# shield.net
KiCad netlist of a schematic drawn in Altium Designer
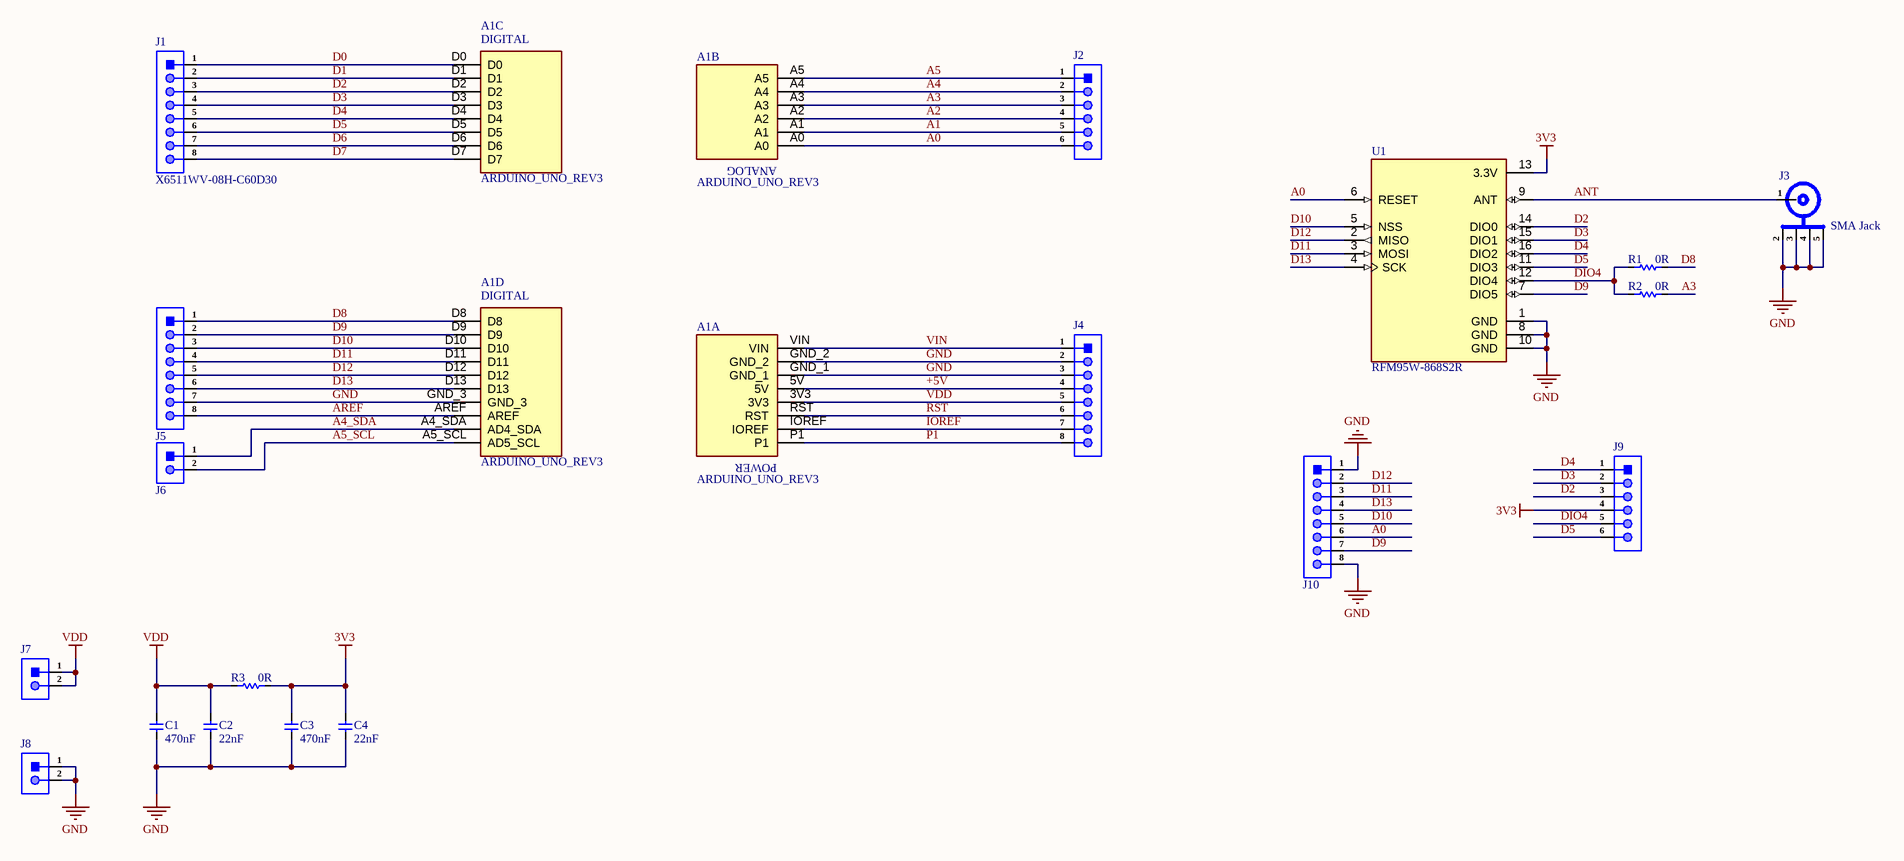
[diagram p0: shield.SchDoc]

(export (version "E")
  (design (tool "Eeschema 10.0.6"))
  (components
    (comp (ref "A1")
      (value "ARDUINO_UNO_REV3")
      (footprint "ARDUINO_ARDUINO_UNO_REV3")
      (description "Microcontroller board based on the ATmega328P.")
      (fields (field (name "MF") "Arduino") (field (name "MP") "ARDUINO UNO REV3"))
      (libsource (lib "") (part "ARDUINO_UNO_REV3_1"))
    )
    (comp (ref "C1")
      (value "470nF")
      (footprint "Cap-0402")
      (description "CAP CER 0.47UF 16V X5R 0402")
      (fields
        (field (name "MANUFACTURER") "Yageo")
        (field (name "MANUFACTURER PART NUMBER") "CC0402KRX5R7BB474")
      )
      (libsource (lib "eSpark Libraries") (part "CC0402KRX5R7BB474"))
    )
    (comp (ref "C2")
      (value "22nF")
      (footprint "Cap-0402")
      (description "CAP CER 0.022UF 16V X7R 0402")
      (fields
        (field (name "MANUFACTURER") "Yageo")
        (field (name "MANUFACTURER PART NUMBER") "CC0402JRX7R7BB223")
      )
      (libsource (lib "eSpark Libraries") (part "CC0402JRX7R7BB223"))
    )
    (comp (ref "C3")
      (value "470nF")
      (footprint "Cap-0402")
      (description "CAP CER 0.47UF 16V X5R 0402")
      (fields
        (field (name "MANUFACTURER") "Yageo")
        (field (name "MANUFACTURER PART NUMBER") "CC0402KRX5R7BB474")
      )
      (libsource (lib "eSpark Libraries") (part "CC0402KRX5R7BB474"))
    )
    (comp (ref "C4")
      (value "22nF")
      (footprint "Cap-0402")
      (description "CAP CER 0.022UF 16V X7R 0402")
      (fields
        (field (name "MANUFACTURER") "Yageo")
        (field (name "MANUFACTURER PART NUMBER") "CC0402JRX7R7BB223")
      )
      (libsource (lib "eSpark Libraries") (part "CC0402JRX7R7BB223"))
    )
    (comp (ref "J1")
      (value "X6511WV-08H-C60D30")
      (footprint "HDR 1x8 TH male")
      (fields (field (name "MANUFACTURER") "XKB") (field (name "LCSC PART NUMBER") "C706880"))
      (libsource (lib "") (part "X6511WV-08H-C60D30_1"))
    )
    (comp (ref "J2")
      (value "X6511WV-06H-C60D30")
      (footprint "HDR1X6_")
      (fields (field (name "MANUFACTURER") "XKB") (field (name "LCSC PART NUMBER") "C706878"))
      (libsource (lib "eSpark Libraries") (part "X6511WV-06H-C60D30"))
    )
    (comp (ref "J3")
      (value "SMA Jack")
      (footprint "CON-SMA-EDGE_S")
      (description "Sma Female Connector, Pcb Edge Mount Rohs Compliant: Yes")
      (fields
        (field (name "MANUFACTURER") "RF Solutions")
        (field (name "MANUFACTURER PART NUMBER") "CON-SMA-EDGE-S")
      )
      (libsource (lib "eSpark Libraries") (part "CON-SMA-EDGE-S"))
    )
    (comp (ref "J4")
      (value "X6511WV-08H-C60D30")
      (footprint "HDR 1x8 TH male")
      (fields (field (name "MANUFACTURER") "XKB") (field (name "LCSC PART NUMBER") "C706880"))
      (libsource (lib "eSpark Libraries") (part "X6511WV-08H-C60D30"))
    )
    (comp (ref "J5")
      (value "X6511WV-08H-C60D30")
      (footprint "HDR 1x8 TH male")
      (fields (field (name "MANUFACTURER") "XKB") (field (name "LCSC PART NUMBER") "C706880"))
      (libsource (lib "") (part "X6511WV-08H-C60D30_1"))
    )
    (comp (ref "J6")
      (value "X6511WV-02H-C60D30")
      (footprint "HDR1X2_")
      (fields (field (name "MANUFACTURER") "XKB") (field (name "LCSC PART NUMBER") "C706874"))
      (libsource (lib "eSpark Libraries") (part "X6511WV-02H-C60D30"))
    )
    (comp (ref "J7")
      (value "X6511WV-02H-C60D30")
      (footprint "HDR1X2_")
      (fields (field (name "MANUFACTURER") "XKB") (field (name "LCSC PART NUMBER") "C706874"))
      (libsource (lib "eSpark Libraries") (part "X6511WV-02H-C60D30"))
    )
    (comp (ref "J8")
      (value "X6511WV-02H-C60D30")
      (footprint "HDR1X2_")
      (fields (field (name "MANUFACTURER") "XKB") (field (name "LCSC PART NUMBER") "C706874"))
      (libsource (lib "eSpark Libraries") (part "X6511WV-02H-C60D30"))
    )
    (comp (ref "J9")
      (value "X6511WV-06H-C60D30")
      (footprint "HDR1X6_")
      (fields (field (name "MANUFACTURER") "XKB") (field (name "LCSC PART NUMBER") "C706878"))
      (libsource (lib "eSpark Libraries") (part "X6511WV-06H-C60D30"))
    )
    (comp (ref "J10")
      (value "X6511WV-08H-C60D30")
      (footprint "HDR 1x8 TH male")
      (fields (field (name "MANUFACTURER") "XKB") (field (name "LCSC PART NUMBER") "C706880"))
      (libsource (lib "") (part "X6511WV-08H-C60D30_1"))
    )
    (comp (ref "R1")
      (value "0R")
      (footprint "Res-0603")
      (description "RES SMD 0R, 1%, 0.1W, 0603")
      (fields
        (field (name "MANUFACTURER") "Yageo")
        (field (name "MANUFACTURER PART NUMBER") "RC0603FR-070RL")
      )
      (libsource (lib "eSpark Libraries") (part "RC0603FR-070RL"))
    )
    (comp (ref "R2")
      (value "0R")
      (footprint "Res-0603")
      (description "RES SMD 0R, 1%, 0.1W, 0603")
      (fields
        (field (name "MANUFACTURER") "Yageo")
        (field (name "MANUFACTURER PART NUMBER") "RC0603FR-070RL")
      )
      (libsource (lib "eSpark Libraries") (part "RC0603FR-070RL"))
    )
    (comp (ref "R3")
      (value "0R")
      (footprint "Res-0603")
      (description "RES SMD 0R, 1%, 0.1W, 0603")
      (fields
        (field (name "MANUFACTURER") "Yageo")
        (field (name "MANUFACTURER PART NUMBER") "RC0603FR-070RL")
      )
      (libsource (lib "eSpark Libraries") (part "RC0603FR-070RL"))
    )
    (comp (ref "U1")
      (value "RFM95W-868S2R")
      (footprint "MODULE_RFM95W-868S2R")
      (description "Module: transceiver; RF; FSK,GFSK,GMSK,LoRa,MSK,OOK; 868MHz; SMD")
      (fields (field (name "MF") "Hope Microelectronics"))
      (libsource (lib "RFM95W-868S2R") (part "RFM95W-868S2R"))
    )
  )
  (nets
    (net (code "1") (name "/+5V") (class "Default")
      (node (ref "A1") (pin "5V") (pinfunction "5V_5V") (pintype "power_in"))
      (node (ref "J4") (pin "4") (pinfunction "4_4") (pintype "passive"))
    )
    (net (code "2") (name "/A0") (class "Default")
      (node (ref "A1") (pin "A0") (pinfunction "A0_A0") (pintype "passive"))
      (node (ref "J10") (pin "6") (pinfunction "6_6") (pintype "passive"))
      (node (ref "J2") (pin "6") (pinfunction "6_6") (pintype "passive"))
      (node (ref "U1") (pin "6") (pinfunction "RESET_6") (pintype "input"))
    )
    (net (code "3") (name "/A1") (class "Default")
      (node (ref "A1") (pin "A1") (pinfunction "A1_A1") (pintype "passive"))
      (node (ref "J2") (pin "5") (pinfunction "5_5") (pintype "passive"))
    )
    (net (code "4") (name "/A2") (class "Default")
      (node (ref "A1") (pin "A2") (pinfunction "A2_A2") (pintype "passive"))
      (node (ref "J2") (pin "4") (pinfunction "4_4") (pintype "passive"))
    )
    (net (code "5") (name "/A3") (class "Default")
      (node (ref "A1") (pin "A3") (pinfunction "A3_A3") (pintype "passive"))
      (node (ref "J2") (pin "3") (pinfunction "3_3") (pintype "passive"))
      (node (ref "R2") (pin "2") (pinfunction "2_2") (pintype "passive"))
    )
    (net (code "6") (name "/A4") (class "Default")
      (node (ref "A1") (pin "A4") (pinfunction "A4_A4") (pintype "passive"))
      (node (ref "J2") (pin "2") (pinfunction "2_2") (pintype "passive"))
    )
    (net (code "7") (name "/A4_SDA") (class "Default")
      (node (ref "A1") (pin "A4_SDA") (pinfunction "AD4_SDA_A4_SDA") (pintype "bidirectional"))
      (node (ref "J6") (pin "1") (pinfunction "1_1") (pintype "passive"))
    )
    (net (code "8") (name "/A5") (class "Default")
      (node (ref "A1") (pin "A5") (pinfunction "A5_A5") (pintype "passive"))
      (node (ref "J2") (pin "1") (pinfunction "1_1") (pintype "passive"))
    )
    (net (code "9") (name "/A5_SCL") (class "Default")
      (node (ref "A1") (pin "A5_SCL") (pinfunction "AD5_SCL_A5_SCL") (pintype "bidirectional"))
      (node (ref "J6") (pin "2") (pinfunction "2_2") (pintype "passive"))
    )
    (net (code "10") (name "/ANT") (class "Default")
      (node (ref "J3") (pin "1") (pinfunction "ANT_1") (pintype "passive"))
      (node (ref "U1") (pin "9") (pinfunction "ANT_9") (pintype "bidirectional"))
    )
    (net (code "11") (name "/AREF") (class "Default")
      (node (ref "A1") (pin "AREF") (pinfunction "AREF_AREF") (pintype "bidirectional"))
      (node (ref "J5") (pin "8") (pinfunction "8_8") (pintype "passive"))
    )
    (net (code "12") (name "/D0") (class "Default")
      (node (ref "A1") (pin "D0") (pinfunction "D0_D0") (pintype "passive"))
      (node (ref "J1") (pin "1") (pinfunction "1_1") (pintype "passive"))
    )
    (net (code "13") (name "/D1") (class "Default")
      (node (ref "A1") (pin "D1") (pinfunction "D1_D1") (pintype "passive"))
      (node (ref "J1") (pin "2") (pinfunction "2_2") (pintype "passive"))
    )
    (net (code "14") (name "/D2") (class "Default")
      (node (ref "A1") (pin "D2") (pinfunction "D2_D2") (pintype "passive"))
      (node (ref "J1") (pin "3") (pinfunction "3_3") (pintype "passive"))
      (node (ref "J9") (pin "3") (pinfunction "3_3") (pintype "passive"))
      (node (ref "U1") (pin "14") (pinfunction "DIO0_14") (pintype "bidirectional"))
    )
    (net (code "15") (name "/D3") (class "Default")
      (node (ref "A1") (pin "D3") (pinfunction "D3_D3") (pintype "passive"))
      (node (ref "J1") (pin "4") (pinfunction "4_4") (pintype "passive"))
      (node (ref "J9") (pin "2") (pinfunction "2_2") (pintype "passive"))
      (node (ref "U1") (pin "15") (pinfunction "DIO1_15") (pintype "bidirectional"))
    )
    (net (code "16") (name "/D4") (class "Default")
      (node (ref "A1") (pin "D4") (pinfunction "D4_D4") (pintype "passive"))
      (node (ref "J1") (pin "5") (pinfunction "5_5") (pintype "passive"))
      (node (ref "J9") (pin "1") (pinfunction "1_1") (pintype "passive"))
      (node (ref "U1") (pin "16") (pinfunction "DIO2_16") (pintype "bidirectional"))
    )
    (net (code "17") (name "/D5") (class "Default")
      (node (ref "A1") (pin "D5") (pinfunction "D5_D5") (pintype "passive"))
      (node (ref "J1") (pin "6") (pinfunction "6_6") (pintype "passive"))
      (node (ref "J9") (pin "6") (pinfunction "6_6") (pintype "passive"))
      (node (ref "U1") (pin "11") (pinfunction "DIO3_11") (pintype "bidirectional"))
    )
    (net (code "18") (name "/D6") (class "Default")
      (node (ref "A1") (pin "D6") (pinfunction "D6_D6") (pintype "passive"))
      (node (ref "J1") (pin "7") (pinfunction "7_7") (pintype "passive"))
    )
    (net (code "19") (name "/D7") (class "Default")
      (node (ref "A1") (pin "D7") (pinfunction "D7_D7") (pintype "passive"))
      (node (ref "J1") (pin "8") (pinfunction "8_8") (pintype "passive"))
    )
    (net (code "20") (name "/D8") (class "Default")
      (node (ref "A1") (pin "D8") (pinfunction "D8_D8") (pintype "bidirectional"))
      (node (ref "J5") (pin "1") (pinfunction "1_1") (pintype "passive"))
      (node (ref "R1") (pin "2") (pinfunction "2_2") (pintype "passive"))
    )
    (net (code "21") (name "/D9") (class "Default")
      (node (ref "A1") (pin "D9") (pinfunction "D9_D9") (pintype "bidirectional"))
      (node (ref "J10") (pin "7") (pinfunction "7_7") (pintype "passive"))
      (node (ref "J5") (pin "2") (pinfunction "2_2") (pintype "passive"))
      (node (ref "U1") (pin "7") (pinfunction "DIO5_7") (pintype "bidirectional"))
    )
    (net (code "22") (name "/D10") (class "Default")
      (node (ref "A1") (pin "D10") (pinfunction "D10_D10") (pintype "bidirectional"))
      (node (ref "J10") (pin "5") (pinfunction "5_5") (pintype "passive"))
      (node (ref "J5") (pin "3") (pinfunction "3_3") (pintype "passive"))
      (node (ref "U1") (pin "5") (pinfunction "NSS_5") (pintype "input"))
    )
    (net (code "23") (name "/D11") (class "Default")
      (node (ref "A1") (pin "D11") (pinfunction "D11_D11") (pintype "bidirectional"))
      (node (ref "J10") (pin "3") (pinfunction "3_3") (pintype "passive"))
      (node (ref "J5") (pin "4") (pinfunction "4_4") (pintype "passive"))
      (node (ref "U1") (pin "3") (pinfunction "MOSI_3") (pintype "input"))
    )
    (net (code "24") (name "/D12") (class "Default")
      (node (ref "A1") (pin "D12") (pinfunction "D12_D12") (pintype "bidirectional"))
      (node (ref "J10") (pin "2") (pinfunction "2_2") (pintype "passive"))
      (node (ref "J5") (pin "5") (pinfunction "5_5") (pintype "passive"))
      (node (ref "U1") (pin "2") (pinfunction "MISO_2") (pintype "output"))
    )
    (net (code "25") (name "/D13") (class "Default")
      (node (ref "A1") (pin "D13") (pinfunction "D13_D13") (pintype "bidirectional"))
      (node (ref "J10") (pin "4") (pinfunction "4_4") (pintype "passive"))
      (node (ref "J5") (pin "6") (pinfunction "6_6") (pintype "passive"))
      (node (ref "U1") (pin "4") (pinfunction "SCK_4") (pintype "input"))
    )
    (net (code "26") (name "/DIO4") (class "Default")
      (node (ref "J9") (pin "5") (pinfunction "5_5") (pintype "passive"))
      (node (ref "R1") (pin "1") (pinfunction "1_1") (pintype "passive"))
      (node (ref "R2") (pin "1") (pinfunction "1_1") (pintype "passive"))
      (node (ref "U1") (pin "12") (pinfunction "DIO4_12") (pintype "bidirectional"))
    )
    (net (code "27") (name "/IOREF") (class "Default")
      (node (ref "A1") (pin "IOREF") (pinfunction "IOREF_IOREF") (pintype "passive"))
      (node (ref "J4") (pin "7") (pinfunction "7_7") (pintype "passive"))
    )
    (net (code "28") (name "/P1") (class "Default")
      (node (ref "A1") (pin "P1") (pinfunction "P1_P1") (pintype "passive"))
      (node (ref "J4") (pin "8") (pinfunction "8_8") (pintype "passive"))
    )
    (net (code "29") (name "/RST") (class "Default")
      (node (ref "A1") (pin "RST") (pinfunction "RST_RST") (pintype "passive"))
      (node (ref "J4") (pin "6") (pinfunction "6_6") (pintype "passive"))
    )
    (net (code "30") (name "/VIN") (class "Default")
      (node (ref "A1") (pin "VIN") (pinfunction "VIN_VIN") (pintype "power_in"))
      (node (ref "J4") (pin "1") (pinfunction "1_1") (pintype "passive"))
    )
    (net (code "31") (name "3V3") (class "Default")
      (node (ref "C3") (pin "2") (pinfunction "2_2") (pintype "passive"))
      (node (ref "C4") (pin "2") (pinfunction "2_2") (pintype "passive"))
      (node (ref "J9") (pin "4") (pinfunction "4_4") (pintype "passive"))
      (node (ref "R3") (pin "2") (pinfunction "2_2") (pintype "passive"))
      (node (ref "U1") (pin "13") (pinfunction "3.3V_13") (pintype "power_in"))
    )
    (net (code "32") (name "GND") (class "Default")
      (node (ref "A1") (pin "GND_1") (pinfunction "GND_1_GND_1") (pintype "power_in"))
      (node (ref "A1") (pin "GND_2") (pinfunction "GND_2_GND_2") (pintype "power_in"))
      (node (ref "A1") (pin "GND_3") (pinfunction "GND_3_GND_3") (pintype "power_in"))
      (node (ref "C1") (pin "1") (pinfunction "1_1") (pintype "passive"))
      (node (ref "C2") (pin "1") (pinfunction "1_1") (pintype "passive"))
      (node (ref "C3") (pin "1") (pinfunction "1_1") (pintype "passive"))
      (node (ref "C4") (pin "1") (pinfunction "1_1") (pintype "passive"))
      (node (ref "J10") (pin "1") (pinfunction "1_1") (pintype "passive"))
      (node (ref "J10") (pin "8") (pinfunction "8_8") (pintype "passive"))
      (node (ref "J3") (pin "2") (pinfunction "GND_2") (pintype "passive"))
      (node (ref "J3") (pin "3") (pinfunction "GND_3") (pintype "passive"))
      (node (ref "J3") (pin "4") (pinfunction "GND_4") (pintype "passive"))
      (node (ref "J3") (pin "5") (pinfunction "GND_5") (pintype "passive"))
      (node (ref "J4") (pin "2") (pinfunction "2_2") (pintype "passive"))
      (node (ref "J4") (pin "3") (pinfunction "3_3") (pintype "passive"))
      (node (ref "J5") (pin "7") (pinfunction "7_7") (pintype "passive"))
      (node (ref "J8") (pin "1") (pinfunction "1_1") (pintype "passive"))
      (node (ref "J8") (pin "2") (pinfunction "2_2") (pintype "passive"))
      (node (ref "U1") (pin "1") (pinfunction "GND_1") (pintype "power_in"))
      (node (ref "U1") (pin "10") (pinfunction "GND_10") (pintype "power_in"))
      (node (ref "U1") (pin "8") (pinfunction "GND_8") (pintype "power_in"))
    )
    (net (code "33") (name "VDD") (class "Default")
      (node (ref "A1") (pin "3V3") (pinfunction "3V3_3V3") (pintype "power_in"))
      (node (ref "C1") (pin "2") (pinfunction "2_2") (pintype "passive"))
      (node (ref "C2") (pin "2") (pinfunction "2_2") (pintype "passive"))
      (node (ref "J4") (pin "5") (pinfunction "5_5") (pintype "passive"))
      (node (ref "J7") (pin "1") (pinfunction "1_1") (pintype "passive"))
      (node (ref "J7") (pin "2") (pinfunction "2_2") (pintype "passive"))
      (node (ref "R3") (pin "1") (pinfunction "1_1") (pintype "passive"))
    )
  )
)
